# SLIM-ADC-16.net
KiCad netlist of a schematic drawn in EAGLE
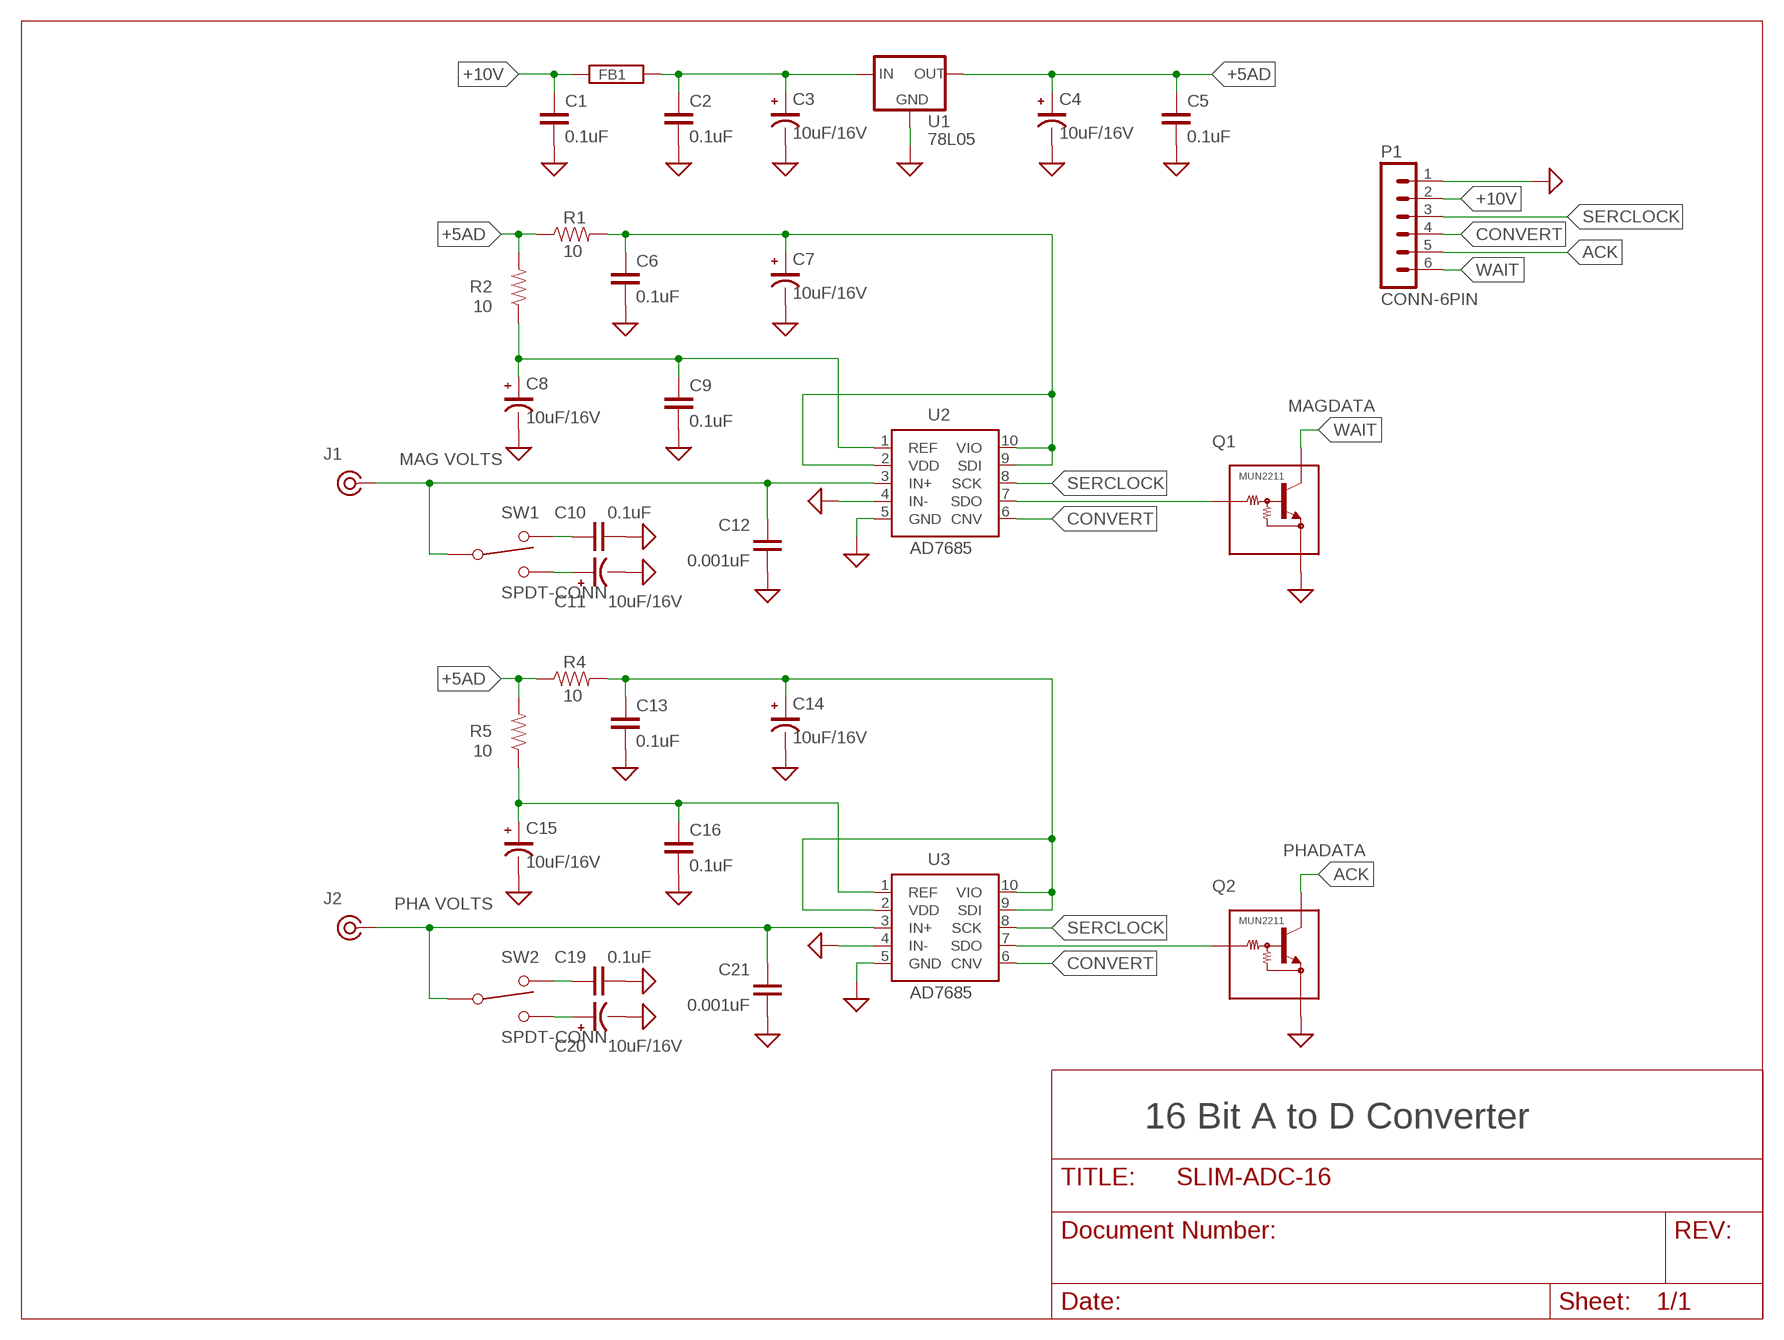
[diagram p0: schematic, sheet 1]

(export (version "E")
  (design (tool "Eeschema 10.0.6"))
  (components
    (comp (ref "C1")
      (value "0.1uF")
      (footprint "eagle-import:0805")
      (libsource (lib "eagle-import") (part "CAP0805"))
    )
    (comp (ref "C2")
      (value "0.1uF")
      (footprint "eagle-import:0805")
      (libsource (lib "eagle-import") (part "CAP0805"))
    )
    (comp (ref "C3")
      (value "10uF/16V")
      (footprint "eagle-import:EIA3216")
      (libsource (lib "eagle-import") (part "CAP-POL1206"))
    )
    (comp (ref "C4")
      (value "10uF/16V")
      (footprint "eagle-import:EIA3216")
      (libsource (lib "eagle-import") (part "CAP-POL1206"))
    )
    (comp (ref "C5")
      (value "0.1uF")
      (footprint "eagle-import:0805")
      (libsource (lib "eagle-import") (part "CAP0805"))
    )
    (comp (ref "C6")
      (value "0.1uF")
      (footprint "eagle-import:0805")
      (libsource (lib "eagle-import") (part "CAP0805"))
    )
    (comp (ref "C7")
      (value "10uF/16V")
      (footprint "eagle-import:EIA3216")
      (libsource (lib "eagle-import") (part "CAP-POL1206"))
    )
    (comp (ref "C8")
      (value "10uF/16V")
      (footprint "eagle-import:EIA3216")
      (libsource (lib "eagle-import") (part "CAP-POL1206"))
    )
    (comp (ref "C9")
      (value "0.1uF")
      (footprint "eagle-import:0805")
      (libsource (lib "eagle-import") (part "CAP0805"))
    )
    (comp (ref "C10")
      (value "0.1uF")
      (footprint "eagle-import:0805")
      (libsource (lib "eagle-import") (part "CAP0805"))
    )
    (comp (ref "C11")
      (value "10uF/16V")
      (footprint "eagle-import:EIA3216")
      (libsource (lib "eagle-import") (part "CAP-POL1206"))
    )
    (comp (ref "C12")
      (value "0.001uF")
      (footprint "eagle-import:0805")
      (libsource (lib "eagle-import") (part "CAP0805"))
    )
    (comp (ref "C13")
      (value "0.1uF")
      (footprint "eagle-import:0805")
      (libsource (lib "eagle-import") (part "CAP0805"))
    )
    (comp (ref "C14")
      (value "10uF/16V")
      (footprint "eagle-import:EIA3216")
      (libsource (lib "eagle-import") (part "CAP-POL1206"))
    )
    (comp (ref "C15")
      (value "10uF/16V")
      (footprint "eagle-import:EIA3216")
      (libsource (lib "eagle-import") (part "CAP-POL1206"))
    )
    (comp (ref "C16")
      (value "0.1uF")
      (footprint "eagle-import:0805")
      (libsource (lib "eagle-import") (part "CAP0805"))
    )
    (comp (ref "C19")
      (value "0.1uF")
      (footprint "eagle-import:0805")
      (libsource (lib "eagle-import") (part "CAP0805"))
    )
    (comp (ref "C20")
      (value "10uF/16V")
      (footprint "eagle-import:EIA3216")
      (libsource (lib "eagle-import") (part "CAP-POL1206"))
    )
    (comp (ref "C21")
      (value "0.001uF")
      (footprint "eagle-import:0805")
      (libsource (lib "eagle-import") (part "CAP0805"))
    )
    (comp (ref "FB1")
      (value "FERRITE0805")
      (footprint "eagle-import:0805")
      (libsource (lib "eagle-import") (part "FERRITE0805"))
    )
    (comp (ref "J1")
      (value "COAX")
      (footprint "eagle-import:SLIM_COAX_PAD")
      (libsource (lib "eagle-import") (part "COAX"))
    )
    (comp (ref "J2")
      (value "COAX")
      (footprint "eagle-import:SLIM_COAX_PAD")
      (libsource (lib "eagle-import") (part "COAX"))
    )
    (comp (ref "P1")
      (value "CONN-6PIN")
      (footprint "eagle-import:CONN-6PIN")
      (libsource (lib "eagle-import") (part "CONN-6PIN"))
    )
    (comp (ref "Q1")
      (value "MUN2211")
      (footprint "eagle-import:SOT23")
      (libsource (lib "eagle-import") (part "MUN2211"))
    )
    (comp (ref "Q2")
      (value "MUN2211")
      (footprint "eagle-import:SOT23")
      (libsource (lib "eagle-import") (part "MUN2211"))
    )
    (comp (ref "R1")
      (value "10")
      (footprint "eagle-import:0805")
      (libsource (lib "eagle-import") (part "RESISTOR0805"))
    )
    (comp (ref "R2")
      (value "10")
      (footprint "eagle-import:0805")
      (libsource (lib "eagle-import") (part "RESISTOR0805"))
    )
    (comp (ref "R4")
      (value "10")
      (footprint "eagle-import:0805")
      (libsource (lib "eagle-import") (part "RESISTOR0805"))
    )
    (comp (ref "R5")
      (value "10")
      (footprint "eagle-import:0805")
      (libsource (lib "eagle-import") (part "RESISTOR0805"))
    )
    (comp (ref "SW1")
      (value "SPDT-CONN")
      (footprint "eagle-import:CONN-3PIN")
      (libsource (lib "eagle-import") (part "SPDT-CONN"))
    )
    (comp (ref "SW2")
      (value "SPDT-CONN")
      (footprint "eagle-import:CONN-3PIN")
      (libsource (lib "eagle-import") (part "SPDT-CONN"))
    )
    (comp (ref "U1")
      (value "78L05")
      (footprint "eagle-import:SOT89")
      (libsource (lib "eagle-import") (part "78MXXLSOT-89"))
    )
    (comp (ref "U2")
      (value "AD7685")
      (footprint "eagle-import:MSOP10")
      (libsource (lib "eagle-import") (part "AD7685"))
    )
    (comp (ref "U3")
      (value "AD7685")
      (footprint "eagle-import:MSOP10")
      (libsource (lib "eagle-import") (part "AD7685"))
    )
  )
  (nets
    (net (code "1") (name "+5AD") (class "Default")
      (node (ref "C4") (pin "A") (pinfunction "+_A") (pintype "passive"))
      (node (ref "C5") (pin "1") (pinfunction "1_1") (pintype "passive"))
      (node (ref "R1") (pin "1") (pinfunction "1_1") (pintype "passive"))
      (node (ref "R2") (pin "2") (pinfunction "2_2") (pintype "passive"))
      (node (ref "R4") (pin "1") (pinfunction "1_1") (pintype "passive"))
      (node (ref "R5") (pin "2") (pinfunction "2_2") (pintype "passive"))
      (node (ref "U1") (pin "1") (pinfunction "OUT_1") (pintype "passive"))
    )
    (net (code "2") (name "+10V") (class "Default")
      (node (ref "C1") (pin "1") (pinfunction "1_1") (pintype "passive"))
      (node (ref "FB1") (pin "1") (pinfunction "P$1_1") (pintype "passive"))
      (node (ref "P1") (pin "2") (pinfunction "2_2") (pintype "passive"))
    )
    (net (code "3") (name "ACK") (class "Default")
      (node (ref "P1") (pin "5") (pinfunction "5_5") (pintype "passive"))
      (node (ref "Q2") (pin "C") (pinfunction "C_C") (pintype "passive"))
    )
    (net (code "4") (name "CONVERT") (class "Default")
      (node (ref "P1") (pin "4") (pinfunction "4_4") (pintype "passive"))
      (node (ref "U2") (pin "6") (pinfunction "CNV_6") (pintype "input"))
      (node (ref "U3") (pin "6") (pinfunction "CNV_6") (pintype "input"))
    )
    (net (code "5") (name "GND") (class "Default")
      (node (ref "C1") (pin "2") (pinfunction "2_2") (pintype "passive"))
      (node (ref "C10") (pin "2") (pinfunction "2_2") (pintype "passive"))
      (node (ref "C11") (pin "C") (pinfunction "-_C") (pintype "passive"))
      (node (ref "C12") (pin "2") (pinfunction "2_2") (pintype "passive"))
      (node (ref "C13") (pin "2") (pinfunction "2_2") (pintype "passive"))
      (node (ref "C14") (pin "C") (pinfunction "-_C") (pintype "passive"))
      (node (ref "C15") (pin "C") (pinfunction "-_C") (pintype "passive"))
      (node (ref "C16") (pin "2") (pinfunction "2_2") (pintype "passive"))
      (node (ref "C19") (pin "2") (pinfunction "2_2") (pintype "passive"))
      (node (ref "C2") (pin "2") (pinfunction "2_2") (pintype "passive"))
      (node (ref "C20") (pin "C") (pinfunction "-_C") (pintype "passive"))
      (node (ref "C21") (pin "2") (pinfunction "2_2") (pintype "passive"))
      (node (ref "C3") (pin "C") (pinfunction "-_C") (pintype "passive"))
      (node (ref "C4") (pin "C") (pinfunction "-_C") (pintype "passive"))
      (node (ref "C5") (pin "2") (pinfunction "2_2") (pintype "passive"))
      (node (ref "C6") (pin "2") (pinfunction "2_2") (pintype "passive"))
      (node (ref "C7") (pin "C") (pinfunction "-_C") (pintype "passive"))
      (node (ref "C8") (pin "C") (pinfunction "-_C") (pintype "passive"))
      (node (ref "C9") (pin "2") (pinfunction "2_2") (pintype "passive"))
      (node (ref "P1") (pin "1") (pinfunction "1_1") (pintype "passive"))
      (node (ref "Q1") (pin "E") (pinfunction "E_E") (pintype "passive"))
      (node (ref "Q2") (pin "E") (pinfunction "E_E") (pintype "passive"))
      (node (ref "U1") (pin "2") (pinfunction "GND_2") (pintype "input"))
      (node (ref "U1") (pin "4") (pinfunction "GND_4") (pintype "input"))
      (node (ref "U2") (pin "4") (pinfunction "IN-_4") (pintype "input"))
      (node (ref "U2") (pin "5") (pinfunction "GND_5") (pintype "power_in"))
      (node (ref "U3") (pin "4") (pinfunction "IN-_4") (pintype "input"))
      (node (ref "U3") (pin "5") (pinfunction "GND_5") (pintype "power_in"))
    )
    (net (code "6") (name "Net-(C3-+)") (class "Default")
      (node (ref "C2") (pin "1") (pinfunction "1_1") (pintype "passive"))
      (node (ref "C3") (pin "A") (pinfunction "+_A") (pintype "passive"))
      (node (ref "FB1") (pin "2") (pinfunction "P$2_2") (pintype "passive"))
      (node (ref "U1") (pin "3") (pinfunction "IN_3") (pintype "input"))
    )
    (net (code "7") (name "Net-(C7-+)") (class "Default")
      (node (ref "C6") (pin "1") (pinfunction "1_1") (pintype "passive"))
      (node (ref "C7") (pin "A") (pinfunction "+_A") (pintype "passive"))
      (node (ref "R1") (pin "2") (pinfunction "2_2") (pintype "passive"))
      (node (ref "U2") (pin "10") (pinfunction "VIO_10") (pintype "power_in"))
      (node (ref "U2") (pin "2") (pinfunction "VDD_2") (pintype "power_in"))
      (node (ref "U2") (pin "9") (pinfunction "SDI_9") (pintype "input"))
    )
    (net (code "8") (name "Net-(C8-+)") (class "Default")
      (node (ref "C8") (pin "A") (pinfunction "+_A") (pintype "passive"))
      (node (ref "C9") (pin "1") (pinfunction "1_1") (pintype "passive"))
      (node (ref "R2") (pin "1") (pinfunction "1_1") (pintype "passive"))
      (node (ref "U2") (pin "1") (pinfunction "REF_1") (pintype "input"))
    )
    (net (code "9") (name "Net-(C10-Pad1)") (class "Default")
      (node (ref "C10") (pin "1") (pinfunction "1_1") (pintype "passive"))
      (node (ref "SW1") (pin "1") (pinfunction "1_1") (pintype "passive"))
    )
    (net (code "10") (name "Net-(C11-+)") (class "Default")
      (node (ref "C11") (pin "A") (pinfunction "+_A") (pintype "passive"))
      (node (ref "SW1") (pin "3") (pinfunction "3_3") (pintype "passive"))
    )
    (net (code "11") (name "Net-(C14-+)") (class "Default")
      (node (ref "C13") (pin "1") (pinfunction "1_1") (pintype "passive"))
      (node (ref "C14") (pin "A") (pinfunction "+_A") (pintype "passive"))
      (node (ref "R4") (pin "2") (pinfunction "2_2") (pintype "passive"))
      (node (ref "U3") (pin "10") (pinfunction "VIO_10") (pintype "power_in"))
      (node (ref "U3") (pin "2") (pinfunction "VDD_2") (pintype "power_in"))
      (node (ref "U3") (pin "9") (pinfunction "SDI_9") (pintype "input"))
    )
    (net (code "12") (name "Net-(C15-+)") (class "Default")
      (node (ref "C15") (pin "A") (pinfunction "+_A") (pintype "passive"))
      (node (ref "C16") (pin "1") (pinfunction "1_1") (pintype "passive"))
      (node (ref "R5") (pin "1") (pinfunction "1_1") (pintype "passive"))
      (node (ref "U3") (pin "1") (pinfunction "REF_1") (pintype "input"))
    )
    (net (code "13") (name "Net-(C19-Pad1)") (class "Default")
      (node (ref "C19") (pin "1") (pinfunction "1_1") (pintype "passive"))
      (node (ref "SW2") (pin "1") (pinfunction "1_1") (pintype "passive"))
    )
    (net (code "14") (name "Net-(C20-+)") (class "Default")
      (node (ref "C20") (pin "A") (pinfunction "+_A") (pintype "passive"))
      (node (ref "SW2") (pin "3") (pinfunction "3_3") (pintype "passive"))
    )
    (net (code "15") (name "Net-(J1A-1)") (class "Default")
      (node (ref "C12") (pin "1") (pinfunction "1_1") (pintype "passive"))
      (node (ref "J1") (pin "P$1") (pinfunction "1_P$1") (pintype "passive"))
      (node (ref "SW1") (pin "2") (pinfunction "2_2") (pintype "passive"))
      (node (ref "U2") (pin "3") (pinfunction "IN+_3") (pintype "input"))
    )
    (net (code "16") (name "Net-(J2A-1)") (class "Default")
      (node (ref "C21") (pin "1") (pinfunction "1_1") (pintype "passive"))
      (node (ref "J2") (pin "P$1") (pinfunction "1_P$1") (pintype "passive"))
      (node (ref "SW2") (pin "2") (pinfunction "2_2") (pintype "passive"))
      (node (ref "U3") (pin "3") (pinfunction "IN+_3") (pintype "input"))
    )
    (net (code "17") (name "Net-(U2-SDO)") (class "Default")
      (node (ref "Q1") (pin "B") (pinfunction "B_B") (pintype "passive"))
      (node (ref "U2") (pin "7") (pinfunction "SDO_7") (pintype "output"))
    )
    (net (code "18") (name "Net-(U3-SDO)") (class "Default")
      (node (ref "Q2") (pin "B") (pinfunction "B_B") (pintype "passive"))
      (node (ref "U3") (pin "7") (pinfunction "SDO_7") (pintype "output"))
    )
    (net (code "19") (name "SERCLOCK") (class "Default")
      (node (ref "P1") (pin "3") (pinfunction "3_3") (pintype "passive"))
      (node (ref "U2") (pin "8") (pinfunction "SCK_8") (pintype "input"))
      (node (ref "U3") (pin "8") (pinfunction "SCK_8") (pintype "input"))
    )
    (net (code "20") (name "WAIT") (class "Default")
      (node (ref "P1") (pin "6") (pinfunction "6_6") (pintype "passive"))
      (node (ref "Q1") (pin "C") (pinfunction "C_C") (pintype "passive"))
    )
  )
)
